# 4Vto3V3_v1_0.net
KiCad netlist of a schematic drawn in Altium Designer
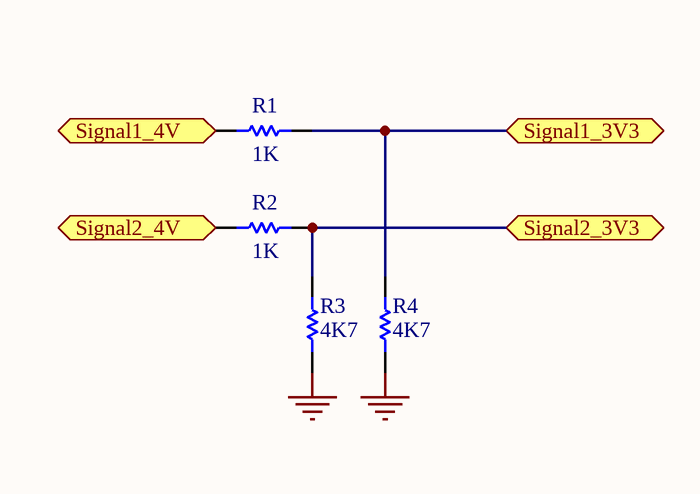
[diagram p0: 4Vto3V3_v1.0.SchDoc]

(export (version "E")
  (design (tool "Eeschema 10.0.6"))
  (components
    (comp (ref "R1")
      (value "1K")
      (footprint "SMD_0805")
      (description "Resistor, 1/4W, 5%")
      (libsource (lib "General") (part "Resistor"))
    )
    (comp (ref "R2")
      (value "1K")
      (footprint "SMD_0805")
      (description "Resistor, 1/4W, 5%")
      (libsource (lib "General") (part "Resistor"))
    )
    (comp (ref "R3")
      (value "4K7")
      (footprint "SMD_0805")
      (description "Resistor, 1/4W, 5%")
      (libsource (lib "General") (part "Resistor"))
    )
    (comp (ref "R4")
      (value "4K7")
      (footprint "SMD_0805")
      (description "Resistor, 1/4W, 5%")
      (libsource (lib "General") (part "Resistor"))
    )
  )
  (nets
    (net (code "1") (name "/Signal1_3V3") (class "Default")
      (node (ref "R1") (pin "2") (pinfunction "2_2") (pintype "passive"))
      (node (ref "R4") (pin "2") (pinfunction "2_2") (pintype "passive"))
    )
    (net (code "2") (name "/Signal1_4V") (class "Default")
      (node (ref "R1") (pin "1") (pinfunction "1_1") (pintype "passive"))
    )
    (net (code "3") (name "/Signal2_3V3") (class "Default")
      (node (ref "R2") (pin "2") (pinfunction "2_2") (pintype "passive"))
      (node (ref "R3") (pin "2") (pinfunction "2_2") (pintype "passive"))
    )
    (net (code "4") (name "/Signal2_4V") (class "Default")
      (node (ref "R2") (pin "1") (pinfunction "1_1") (pintype "passive"))
    )
    (net (code "5") (name "GND") (class "Default")
      (node (ref "R3") (pin "1") (pinfunction "1_1") (pintype "passive"))
      (node (ref "R4") (pin "1") (pinfunction "1_1") (pintype "passive"))
    )
  )
)
